# test_nano.net
KiCad netlist of a schematic drawn in EAGLE
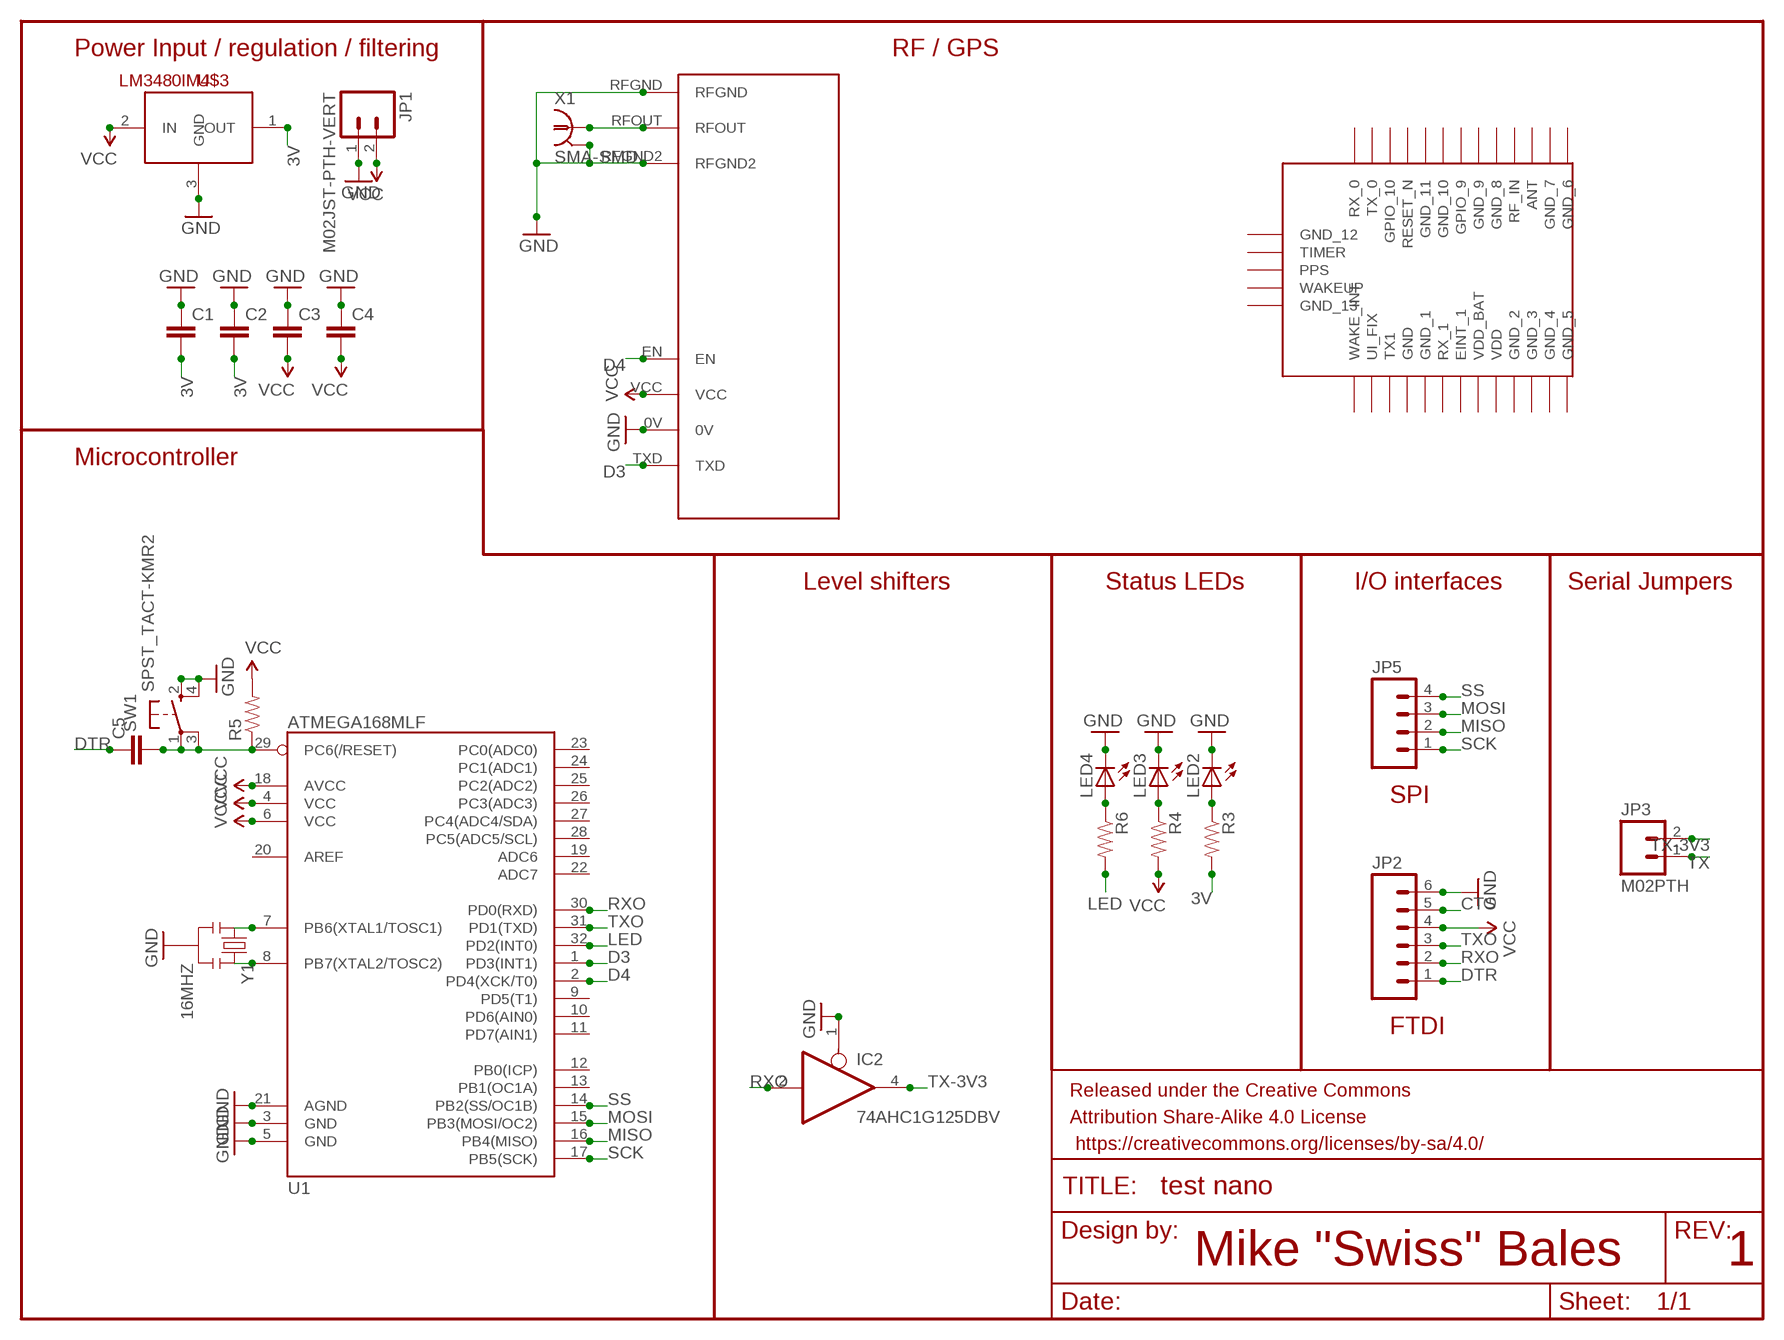
[diagram p0: schematic, sheet 1]

(export (version "E")
  (design (tool "Eeschema 10.0.6"))
  (components
    (comp (ref "C1")
      (value "CAP0805")
      (footprint "eagle-import:0805")
      (libsource (lib "eagle-import") (part "CAP0805"))
    )
    (comp (ref "C2")
      (value "CAP0805")
      (footprint "eagle-import:0805")
      (libsource (lib "eagle-import") (part "CAP0805"))
    )
    (comp (ref "C3")
      (value "CAP0805")
      (footprint "eagle-import:0805")
      (libsource (lib "eagle-import") (part "CAP0805"))
    )
    (comp (ref "C4")
      (value "CAP0805")
      (footprint "eagle-import:0805")
      (libsource (lib "eagle-import") (part "CAP0805"))
    )
    (comp (ref "C5")
      (value "CAP0805")
      (footprint "eagle-import:0805")
      (libsource (lib "eagle-import") (part "CAP0805"))
    )
    (comp (ref "FRAME1")
      (value "FRAME-LETTER")
      (footprint "eagle-import:CREATIVE_COMMONS")
      (libsource (lib "eagle-import") (part "FRAME-LETTER"))
    )
    (comp (ref "IC2")
      (value "74AHC1G125DBV")
      (footprint "eagle-import:SOT23-5")
      (libsource (lib "eagle-import") (part "741G125DBVAHC"))
    )
    (comp (ref "JP1")
      (value "M02JST-PTH-VERT")
      (footprint "eagle-import:JST-2-PTH-VERT")
      (libsource (lib "eagle-import") (part "M02JST-PTH-VERT"))
    )
    (comp (ref "JP2")
      (value "M06NO_SILK_FEMALE_PTH")
      (footprint "eagle-import:1X06_NO_SILK")
      (libsource (lib "eagle-import") (part "M06NO_SILK_FEMALE_PTH"))
    )
    (comp (ref "JP3")
      (value "M02PTH")
      (footprint "eagle-import:1X02")
      (libsource (lib "eagle-import") (part "M02PTH"))
    )
    (comp (ref "JP5")
      (value "M041X04_NO_SILK")
      (footprint "eagle-import:1X04_NO_SILK")
      (libsource (lib "eagle-import") (part "M041X04_NO_SILK"))
    )
    (comp (ref "LED2")
      (value "LEDCHIP-LED0805")
      (footprint "eagle-import:CHIP-LED0805")
      (libsource (lib "eagle-import") (part "LEDCHIP-LED0805"))
    )
    (comp (ref "LED3")
      (value "LEDCHIP-LED0805")
      (footprint "eagle-import:CHIP-LED0805")
      (libsource (lib "eagle-import") (part "LEDCHIP-LED0805"))
    )
    (comp (ref "LED4")
      (value "LEDCHIP-LED0805")
      (footprint "eagle-import:CHIP-LED0805")
      (libsource (lib "eagle-import") (part "LEDCHIP-LED0805"))
    )
    (comp (ref "R3")
      (value "RESISTOR0805-RES")
      (footprint "eagle-import:0805")
      (libsource (lib "eagle-import") (part "RESISTOR0805-RES"))
    )
    (comp (ref "R4")
      (value "RESISTOR0805-RES")
      (footprint "eagle-import:0805")
      (libsource (lib "eagle-import") (part "RESISTOR0805-RES"))
    )
    (comp (ref "R5")
      (value "RESISTOR0805-RES")
      (footprint "eagle-import:0805")
      (libsource (lib "eagle-import") (part "RESISTOR0805-RES"))
    )
    (comp (ref "R6")
      (value "RESISTOR0805-RES")
      (footprint "eagle-import:0805")
      (libsource (lib "eagle-import") (part "RESISTOR0805-RES"))
    )
    (comp (ref "SW1")
      (value "SPST_TACT-KMR2")
      (footprint "eagle-import:KMR2")
      (libsource (lib "eagle-import") (part "SPST_TACT-KMR2"))
    )
    (comp (ref "U$1")
      (value "UBLOXUC530")
      (footprint "eagle-import:UBLOXUC530")
      (libsource (lib "eagle-import") (part "UBLOXUC530"))
    )
    (comp (ref "U$2")
      (value "RADIOMETRIX-HX1")
      (footprint "eagle-import:RADIOMETRIX-HX1")
      (libsource (lib "eagle-import") (part "RADIOMETRIX-HX1"))
    )
    (comp (ref "U$3")
      (value "LM3480IM4")
      (footprint "eagle-import:SOT23-3")
      (libsource (lib "eagle-import") (part "LM3480IM4"))
    )
    (comp (ref "U1")
      (value "ATMEGA168MLF")
      (footprint "eagle-import:MLF32")
      (libsource (lib "eagle-import") (part "ATMEGA168MLF"))
    )
    (comp (ref "X1")
      (value "SMA-SMD")
      (footprint "eagle-import:SMA-SMD")
      (libsource (lib "eagle-import") (part "SMA-SMD"))
    )
    (comp (ref "Y1")
      (value "16MHZ")
      (footprint "eagle-import:RESONATOR-SMD")
      (libsource (lib "eagle-import") (part "RESONATOR16MHZ"))
    )
  )
  (nets
    (net (code "1") (name "/3V") (class "Default")
      (node (ref "C1") (pin "2") (pinfunction "2_2") (pintype "passive"))
      (node (ref "C2") (pin "2") (pinfunction "2_2") (pintype "passive"))
      (node (ref "R3") (pin "2") (pinfunction "2_2") (pintype "passive"))
      (node (ref "U$3") (pin "1") (pinfunction "OUT_1") (pintype "bidirectional"))
    )
    (net (code "2") (name "/CTS") (class "Default")
      (node (ref "JP2") (pin "5") (pinfunction "5_5") (pintype "passive"))
    )
    (net (code "3") (name "/D3") (class "Default")
      (node (ref "U$2") (pin "TXD") (pinfunction "TXD_TXD") (pintype "bidirectional"))
      (node (ref "U1") (pin "1") (pinfunction "PD3(INT1)_1") (pintype "bidirectional"))
    )
    (net (code "4") (name "/D4") (class "Default")
      (node (ref "U$2") (pin "EN") (pinfunction "EN_EN") (pintype "bidirectional"))
      (node (ref "U1") (pin "2") (pinfunction "PD4(XCK/T0)_2") (pintype "bidirectional"))
    )
    (net (code "5") (name "/DTR") (class "Default")
      (node (ref "C5") (pin "1") (pinfunction "1_1") (pintype "passive"))
      (node (ref "JP2") (pin "1") (pinfunction "1_1") (pintype "passive"))
    )
    (net (code "6") (name "/LED") (class "Default")
      (node (ref "R6") (pin "2") (pinfunction "2_2") (pintype "passive"))
      (node (ref "U1") (pin "32") (pinfunction "PD2(INT0)_32") (pintype "bidirectional"))
    )
    (net (code "7") (name "/MISO") (class "Default")
      (node (ref "JP5") (pin "2") (pinfunction "2_2") (pintype "passive"))
      (node (ref "U1") (pin "16") (pinfunction "PB4(MISO)_16") (pintype "bidirectional"))
    )
    (net (code "8") (name "/MOSI") (class "Default")
      (node (ref "JP5") (pin "3") (pinfunction "3_3") (pintype "passive"))
      (node (ref "U1") (pin "15") (pinfunction "PB3(MOSI/OC2)_15") (pintype "bidirectional"))
    )
    (net (code "9") (name "/RXO") (class "Default")
      (node (ref "IC2") (pin "2") (pinfunction "I_2") (pintype "input"))
      (node (ref "JP2") (pin "2") (pinfunction "2_2") (pintype "passive"))
      (node (ref "U1") (pin "30") (pinfunction "PD0(RXD)_30") (pintype "bidirectional"))
    )
    (net (code "10") (name "/SCK") (class "Default")
      (node (ref "JP5") (pin "1") (pinfunction "1_1") (pintype "passive"))
      (node (ref "U1") (pin "17") (pinfunction "PB5(SCK)_17") (pintype "bidirectional"))
    )
    (net (code "11") (name "/SS") (class "Default")
      (node (ref "JP5") (pin "4") (pinfunction "4_4") (pintype "passive"))
      (node (ref "U1") (pin "14") (pinfunction "PB2(SS/OC1B)_14") (pintype "bidirectional"))
    )
    (net (code "12") (name "/TX") (class "Default")
      (node (ref "JP3") (pin "1") (pinfunction "1_1") (pintype "passive"))
    )
    (net (code "13") (name "/TX-3V3") (class "Default")
      (node (ref "IC2") (pin "4") (pinfunction "O_4") (pintype "tri_state"))
      (node (ref "JP3") (pin "2") (pinfunction "2_2") (pintype "passive"))
    )
    (net (code "14") (name "/TXO") (class "Default")
      (node (ref "JP2") (pin "3") (pinfunction "3_3") (pintype "passive"))
      (node (ref "U1") (pin "31") (pinfunction "PD1(TXD)_31") (pintype "bidirectional"))
    )
    (net (code "15") (name "GND") (class "Default")
      (node (ref "C1") (pin "1") (pinfunction "1_1") (pintype "passive"))
      (node (ref "C2") (pin "1") (pinfunction "1_1") (pintype "passive"))
      (node (ref "C3") (pin "1") (pinfunction "1_1") (pintype "passive"))
      (node (ref "C4") (pin "1") (pinfunction "1_1") (pintype "passive"))
      (node (ref "IC2") (pin "1") (pinfunction "OE_1") (pintype "input"))
      (node (ref "JP1") (pin "1") (pinfunction "1_1") (pintype "passive"))
      (node (ref "JP2") (pin "6") (pinfunction "6_6") (pintype "passive"))
      (node (ref "LED2") (pin "C") (pinfunction "C_C") (pintype "passive"))
      (node (ref "LED3") (pin "C") (pinfunction "C_C") (pintype "passive"))
      (node (ref "LED4") (pin "C") (pinfunction "C_C") (pintype "passive"))
      (node (ref "SW1") (pin "2") (pinfunction "S_2") (pintype "passive"))
      (node (ref "SW1") (pin "4") (pinfunction "S1_4") (pintype "passive"))
      (node (ref "U$2") (pin "0V") (pinfunction "0V_0V") (pintype "bidirectional"))
      (node (ref "U$2") (pin "RFGND") (pinfunction "RFGND_RFGND") (pintype "bidirectional"))
      (node (ref "U$2") (pin "RFGND2") (pinfunction "RFGND2_RFGND2") (pintype "bidirectional"))
      (node (ref "U$3") (pin "3") (pinfunction "GND_3") (pintype "bidirectional"))
      (node (ref "U1") (pin "21") (pinfunction "AGND_21") (pintype "bidirectional"))
      (node (ref "U1") (pin "3") (pinfunction "GND_3") (pintype "bidirectional"))
      (node (ref "U1") (pin "5") (pinfunction "GND_5") (pintype "bidirectional"))
      (node (ref "X1") (pin "2@1") (pinfunction "2_2@1") (pintype "passive"))
      (node (ref "X1") (pin "2@2") (pinfunction "2_2@2") (pintype "passive"))
      (node (ref "X1") (pin "2@3") (pinfunction "2_2@3") (pintype "passive"))
      (node (ref "X1") (pin "2@4") (pinfunction "2_2@4") (pintype "passive"))
      (node (ref "X1") (pin "2@5") (pinfunction "2_2@5") (pintype "passive"))
      (node (ref "X1") (pin "2@6") (pinfunction "2_2@6") (pintype "passive"))
      (node (ref "Y1") (pin "2") (pinfunction "2_2") (pintype "passive"))
    )
    (net (code "16") (name "Net-(LED2-PadA)") (class "Default")
      (node (ref "LED2") (pin "A") (pinfunction "A_A") (pintype "passive"))
      (node (ref "R3") (pin "1") (pinfunction "1_1") (pintype "passive"))
    )
    (net (code "17") (name "Net-(LED3-PadA)") (class "Default")
      (node (ref "LED3") (pin "A") (pinfunction "A_A") (pintype "passive"))
      (node (ref "R4") (pin "1") (pinfunction "1_1") (pintype "passive"))
    )
    (net (code "18") (name "Net-(LED4-PadA)") (class "Default")
      (node (ref "LED4") (pin "A") (pinfunction "A_A") (pintype "passive"))
      (node (ref "R6") (pin "1") (pinfunction "1_1") (pintype "passive"))
    )
    (net (code "19") (name "Net-(SW1-P)") (class "Default")
      (node (ref "C5") (pin "2") (pinfunction "2_2") (pintype "passive"))
      (node (ref "R5") (pin "1") (pinfunction "1_1") (pintype "passive"))
      (node (ref "SW1") (pin "1") (pinfunction "P_1") (pintype "passive"))
      (node (ref "SW1") (pin "3") (pinfunction "P1_3") (pintype "passive"))
      (node (ref "U1") (pin "29") (pinfunction "PC6(/RESET)_29") (pintype "bidirectional"))
    )
    (net (code "20") (name "Net-(U$2-PadRFOUT)") (class "Default")
      (node (ref "U$2") (pin "RFOUT") (pinfunction "RFOUT_RFOUT") (pintype "bidirectional"))
      (node (ref "X1") (pin "1") (pinfunction "1_1") (pintype "passive"))
    )
    (net (code "21") (name "Net-(U1-PB6(XTAL1{slash}TOSC1))") (class "Default")
      (node (ref "U1") (pin "7") (pinfunction "PB6(XTAL1/TOSC1)_7") (pintype "bidirectional"))
      (node (ref "Y1") (pin "1") (pinfunction "1_1") (pintype "passive"))
    )
    (net (code "22") (name "Net-(U1-PB7(XTAL2{slash}TOSC2))") (class "Default")
      (node (ref "U1") (pin "8") (pinfunction "PB7(XTAL2/TOSC2)_8") (pintype "bidirectional"))
      (node (ref "Y1") (pin "3") (pinfunction "3_3") (pintype "passive"))
    )
    (net (code "23") (name "VCC") (class "Default")
      (node (ref "C3") (pin "2") (pinfunction "2_2") (pintype "passive"))
      (node (ref "C4") (pin "2") (pinfunction "2_2") (pintype "passive"))
      (node (ref "JP1") (pin "2") (pinfunction "2_2") (pintype "passive"))
      (node (ref "JP2") (pin "4") (pinfunction "4_4") (pintype "passive"))
      (node (ref "R4") (pin "2") (pinfunction "2_2") (pintype "passive"))
      (node (ref "R5") (pin "2") (pinfunction "2_2") (pintype "passive"))
      (node (ref "U$2") (pin "VCC") (pinfunction "VCC_VCC") (pintype "bidirectional"))
      (node (ref "U$3") (pin "2") (pinfunction "IN_2") (pintype "bidirectional"))
      (node (ref "U1") (pin "18") (pinfunction "AVCC_18") (pintype "bidirectional"))
      (node (ref "U1") (pin "4") (pinfunction "VCC_4") (pintype "bidirectional"))
      (node (ref "U1") (pin "6") (pinfunction "VCC_6") (pintype "bidirectional"))
    )
    (net (code "24") (name "unconnected-(U$1-ANT-PadPANT)") (class "Default")
      (node (ref "U$1") (pin "PANT") (pinfunction "ANT_PANT") (pintype "bidirectional"))
    )
    (net (code "25") (name "unconnected-(U$1-PadEINT_1)") (class "Default")
      (node (ref "U$1") (pin "EINT_1") (pinfunction "EINT_1_EINT_1") (pintype "bidirectional"))
    )
    (net (code "26") (name "unconnected-(U$1-PadGND)") (class "Default")
      (node (ref "U$1") (pin "GND") (pinfunction "GND_GND") (pintype "bidirectional"))
    )
    (net (code "27") (name "unconnected-(U$1-PadGND_1)") (class "Default")
      (node (ref "U$1") (pin "GND_1") (pinfunction "GND_1_GND_1") (pintype "bidirectional"))
    )
    (net (code "28") (name "unconnected-(U$1-PadGND_2)") (class "Default")
      (node (ref "U$1") (pin "GND_2") (pinfunction "GND_2_GND_2") (pintype "bidirectional"))
    )
    (net (code "29") (name "unconnected-(U$1-PadGND_3)") (class "Default")
      (node (ref "U$1") (pin "GND_3") (pinfunction "GND_3_GND_3") (pintype "bidirectional"))
    )
    (net (code "30") (name "unconnected-(U$1-PadGND_4)") (class "Default")
      (node (ref "U$1") (pin "GND_4") (pinfunction "GND_4_GND_4") (pintype "bidirectional"))
    )
    (net (code "31") (name "unconnected-(U$1-PadGND_5)") (class "Default")
      (node (ref "U$1") (pin "GND_5") (pinfunction "GND_5_GND_5") (pintype "bidirectional"))
    )
    (net (code "32") (name "unconnected-(U$1-PadGND_6)") (class "Default")
      (node (ref "U$1") (pin "GND_6") (pinfunction "GND_6_GND_6") (pintype "bidirectional"))
    )
    (net (code "33") (name "unconnected-(U$1-PadGND_7)") (class "Default")
      (node (ref "U$1") (pin "GND_7") (pinfunction "GND_7_GND_7") (pintype "bidirectional"))
    )
    (net (code "34") (name "unconnected-(U$1-PadGND_8)") (class "Default")
      (node (ref "U$1") (pin "GND_8") (pinfunction "GND_8_GND_8") (pintype "bidirectional"))
    )
    (net (code "35") (name "unconnected-(U$1-PadGND_9)") (class "Default")
      (node (ref "U$1") (pin "GND_9") (pinfunction "GND_9_GND_9") (pintype "no_connect"))
    )
    (net (code "36") (name "unconnected-(U$1-PadGND_10)") (class "Default")
      (node (ref "U$1") (pin "GND_10") (pinfunction "GND_10_GND_10") (pintype "bidirectional"))
    )
    (net (code "37") (name "unconnected-(U$1-PadGND_11)") (class "Default")
      (node (ref "U$1") (pin "GND_11") (pinfunction "GND_11_GND_11") (pintype "bidirectional"))
    )
    (net (code "38") (name "unconnected-(U$1-PadGND_12)") (class "Default")
      (node (ref "U$1") (pin "GND_12") (pinfunction "GND_12_GND_12") (pintype "bidirectional"))
    )
    (net (code "39") (name "unconnected-(U$1-PadGND_13)") (class "Default")
      (node (ref "U$1") (pin "GND_13") (pinfunction "GND_13_GND_13") (pintype "bidirectional"))
    )
    (net (code "40") (name "unconnected-(U$1-PadGPIO_9)") (class "Default")
      (node (ref "U$1") (pin "GPIO_9") (pinfunction "GPIO_9_GPIO_9") (pintype "bidirectional"))
    )
    (net (code "41") (name "unconnected-(U$1-PadGPIO_10)") (class "Default")
      (node (ref "U$1") (pin "GPIO_10") (pinfunction "GPIO_10_GPIO_10") (pintype "bidirectional"))
    )
    (net (code "42") (name "unconnected-(U$1-PadPPS)") (class "Default")
      (node (ref "U$1") (pin "PPS") (pinfunction "PPS_PPS") (pintype "bidirectional"))
    )
    (net (code "43") (name "unconnected-(U$1-PadRESET_N)") (class "Default")
      (node (ref "U$1") (pin "RESET_N") (pinfunction "RESET_N_RESET_N") (pintype "bidirectional"))
    )
    (net (code "44") (name "unconnected-(U$1-PadRF_IN)") (class "Default")
      (node (ref "U$1") (pin "RF_IN") (pinfunction "RF_IN_RF_IN") (pintype "bidirectional"))
    )
    (net (code "45") (name "unconnected-(U$1-PadRX_0)") (class "Default")
      (node (ref "U$1") (pin "RX_0") (pinfunction "RX_0_RX_0") (pintype "bidirectional"))
    )
    (net (code "46") (name "unconnected-(U$1-PadRX_1)") (class "Default")
      (node (ref "U$1") (pin "RX_1") (pinfunction "RX_1_RX_1") (pintype "bidirectional"))
    )
    (net (code "47") (name "unconnected-(U$1-PadTIMER)") (class "Default")
      (node (ref "U$1") (pin "TIMER") (pinfunction "TIMER_TIMER") (pintype "bidirectional"))
    )
    (net (code "48") (name "unconnected-(U$1-PadTX1)") (class "Default")
      (node (ref "U$1") (pin "TX1") (pinfunction "TX1_TX1") (pintype "bidirectional"))
    )
    (net (code "49") (name "unconnected-(U$1-PadTX_0)") (class "Default")
      (node (ref "U$1") (pin "TX_0") (pinfunction "TX_0_TX_0") (pintype "bidirectional"))
    )
    (net (code "50") (name "unconnected-(U$1-PadUI_FIX)") (class "Default")
      (node (ref "U$1") (pin "UI_FIX") (pinfunction "UI_FIX_UI_FIX") (pintype "bidirectional"))
    )
    (net (code "51") (name "unconnected-(U$1-PadVDD)") (class "Default")
      (node (ref "U$1") (pin "VDD") (pinfunction "VDD_VDD") (pintype "bidirectional"))
    )
    (net (code "52") (name "unconnected-(U$1-PadVDD_BAT)") (class "Default")
      (node (ref "U$1") (pin "VDD_BAT") (pinfunction "VDD_BAT_VDD_BAT") (pintype "no_connect"))
    )
    (net (code "53") (name "unconnected-(U$1-PadWAKEUP)") (class "Default")
      (node (ref "U$1") (pin "WAKEUP") (pinfunction "WAKEUP_WAKEUP") (pintype "bidirectional"))
    )
    (net (code "54") (name "unconnected-(U$1-PadWAKE_INT)") (class "Default")
      (node (ref "U$1") (pin "WAKE_INT") (pinfunction "WAKE_INT_WAKE_INT") (pintype "bidirectional"))
    )
    (net (code "55") (name "unconnected-(U1-ADC6-Pad19)") (class "Default")
      (node (ref "U1") (pin "19") (pinfunction "ADC6_19") (pintype "bidirectional"))
    )
    (net (code "56") (name "unconnected-(U1-ADC7-Pad22)") (class "Default")
      (node (ref "U1") (pin "22") (pinfunction "ADC7_22") (pintype "bidirectional"))
    )
    (net (code "57") (name "unconnected-(U1-AREF-Pad20)") (class "Default")
      (node (ref "U1") (pin "20") (pinfunction "AREF_20") (pintype "bidirectional"))
    )
    (net (code "58") (name "unconnected-(U1-PB0(ICP)-Pad12)") (class "Default")
      (node (ref "U1") (pin "12") (pinfunction "PB0(ICP)_12") (pintype "bidirectional"))
    )
    (net (code "59") (name "unconnected-(U1-PB1(OC1A)-Pad13)") (class "Default")
      (node (ref "U1") (pin "13") (pinfunction "PB1(OC1A)_13") (pintype "bidirectional"))
    )
    (net (code "60") (name "unconnected-(U1-PC0(ADC0)-Pad23)") (class "Default")
      (node (ref "U1") (pin "23") (pinfunction "PC0(ADC0)_23") (pintype "bidirectional"))
    )
    (net (code "61") (name "unconnected-(U1-PC1(ADC1)-Pad24)") (class "Default")
      (node (ref "U1") (pin "24") (pinfunction "PC1(ADC1)_24") (pintype "bidirectional"))
    )
    (net (code "62") (name "unconnected-(U1-PC2(ADC2)-Pad25)") (class "Default")
      (node (ref "U1") (pin "25") (pinfunction "PC2(ADC2)_25") (pintype "bidirectional"))
    )
    (net (code "63") (name "unconnected-(U1-PC3(ADC3)-Pad26)") (class "Default")
      (node (ref "U1") (pin "26") (pinfunction "PC3(ADC3)_26") (pintype "bidirectional"))
    )
    (net (code "64") (name "unconnected-(U1-PC4(ADC4{slash}SDA)-Pad27)") (class "Default")
      (node (ref "U1") (pin "27") (pinfunction "PC4(ADC4/SDA)_27") (pintype "bidirectional"))
    )
    (net (code "65") (name "unconnected-(U1-PC5(ADC5{slash}SCL)-Pad28)") (class "Default")
      (node (ref "U1") (pin "28") (pinfunction "PC5(ADC5/SCL)_28") (pintype "bidirectional"))
    )
    (net (code "66") (name "unconnected-(U1-PD5(T1)-Pad9)") (class "Default")
      (node (ref "U1") (pin "9") (pinfunction "PD5(T1)_9") (pintype "bidirectional"))
    )
    (net (code "67") (name "unconnected-(U1-PD6(AIN0)-Pad10)") (class "Default")
      (node (ref "U1") (pin "10") (pinfunction "PD6(AIN0)_10") (pintype "bidirectional"))
    )
    (net (code "68") (name "unconnected-(U1-PD7(AIN1)-Pad11)") (class "Default")
      (node (ref "U1") (pin "11") (pinfunction "PD7(AIN1)_11") (pintype "bidirectional"))
    )
  )
)
